# PCB-JACKGPO.net
KiCad netlist of a schematic drawn in EAGLE
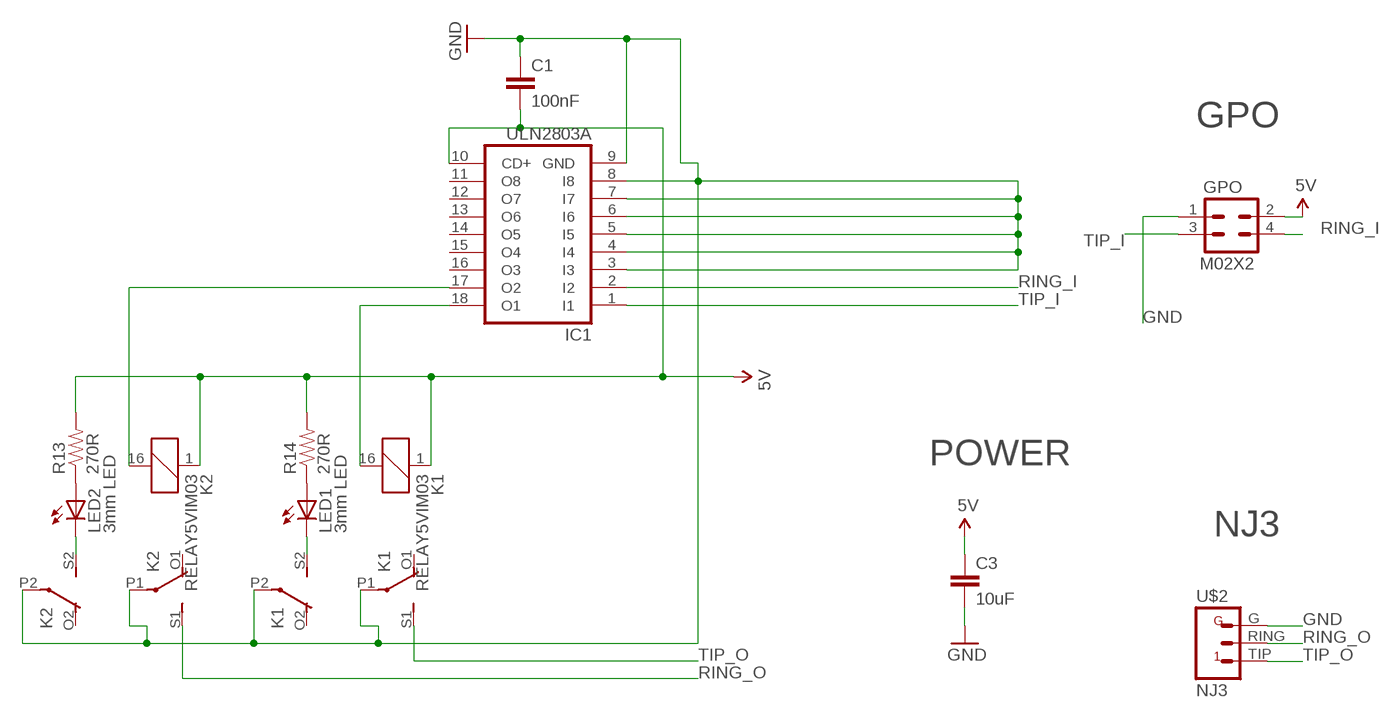
[diagram p0: schematic, sheet 1]

(export (version "E")
  (design (tool "Eeschema 10.0.6"))
  (components
    (comp (ref "C1")
      (value "100nF")
      (footprint "eagle-import:0805")
      (libsource (lib "eagle-import") (part "CAP0805"))
    )
    (comp (ref "C3")
      (value "10uF")
      (footprint "eagle-import:0805")
      (libsource (lib "eagle-import") (part "CAP0805"))
    )
    (comp (ref "GPO")
      (value "M02X2")
      (footprint "eagle-import:2X2")
      (libsource (lib "eagle-import") (part "M02X2"))
    )
    (comp (ref "IC1")
      (value "ULN2803A")
      (footprint "eagle-import:SO18W")
      (libsource (lib "eagle-import") (part "ULN2803ASO18W"))
    )
    (comp (ref "K1")
      (value "RELAY5VIM03")
      (footprint "eagle-import:DS2Y")
      (libsource (lib "eagle-import") (part "RELAY5VIM03"))
    )
    (comp (ref "K2")
      (value "RELAY5VIM03")
      (footprint "eagle-import:DS2Y")
      (libsource (lib "eagle-import") (part "RELAY5VIM03"))
    )
    (comp (ref "LED1")
      (value "3mm LED")
      (footprint "eagle-import:LED3MM")
      (libsource (lib "eagle-import") (part "LED3MM"))
    )
    (comp (ref "LED2")
      (value "3mm LED")
      (footprint "eagle-import:LED3MM")
      (libsource (lib "eagle-import") (part "LED3MM"))
    )
    (comp (ref "R13")
      (value "270R")
      (footprint "eagle-import:0603-RES")
      (libsource (lib "eagle-import") (part "RESISTOR0603-RES"))
    )
    (comp (ref "R14")
      (value "270R")
      (footprint "eagle-import:0603-RES")
      (libsource (lib "eagle-import") (part "RESISTOR0603-RES"))
    )
    (comp (ref "U$2")
      (value "NJ3")
      (footprint "eagle-import:NJ3FP6C")
      (libsource (lib "eagle-import") (part "NJ3"))
    )
  )
  (nets
    (net (code "1") (name "/RING_I") (class "Default")
      (node (ref "GPO") (pin "4") (pinfunction "4_4") (pintype "passive"))
      (node (ref "IC1") (pin "2") (pinfunction "I2_2") (pintype "input"))
    )
    (net (code "2") (name "/RING_O") (class "Default")
      (node (ref "K2") (pin "S1") (pinfunction "S_S1") (pintype "passive"))
      (node (ref "U$2") (pin "RING") (pinfunction "2_RING") (pintype "passive"))
    )
    (net (code "3") (name "/TIP_I") (class "Default")
      (node (ref "GPO") (pin "3") (pinfunction "3_3") (pintype "passive"))
      (node (ref "IC1") (pin "1") (pinfunction "I1_1") (pintype "input"))
    )
    (net (code "4") (name "/TIP_O") (class "Default")
      (node (ref "K1") (pin "S1") (pinfunction "S_S1") (pintype "passive"))
      (node (ref "U$2") (pin "TIP") (pinfunction "1_TIP") (pintype "passive"))
    )
    (net (code "5") (name "5V") (class "Default")
      (node (ref "C1") (pin "2") (pinfunction "2_2") (pintype "passive"))
      (node (ref "C3") (pin "1") (pinfunction "1_1") (pintype "passive"))
      (node (ref "GPO") (pin "2") (pinfunction "2_2") (pintype "passive"))
      (node (ref "IC1") (pin "10") (pinfunction "CD+_10") (pintype "passive"))
      (node (ref "K1") (pin "1") (pinfunction "1_1") (pintype "passive"))
      (node (ref "K2") (pin "1") (pinfunction "1_1") (pintype "passive"))
      (node (ref "R13") (pin "2") (pinfunction "2_2") (pintype "passive"))
      (node (ref "R14") (pin "2") (pinfunction "2_2") (pintype "passive"))
    )
    (net (code "6") (name "GND") (class "Default")
      (node (ref "C1") (pin "1") (pinfunction "1_1") (pintype "passive"))
      (node (ref "C3") (pin "2") (pinfunction "2_2") (pintype "passive"))
      (node (ref "GPO") (pin "1") (pinfunction "1_1") (pintype "passive"))
      (node (ref "IC1") (pin "3") (pinfunction "I3_3") (pintype "input"))
      (node (ref "IC1") (pin "4") (pinfunction "I4_4") (pintype "input"))
      (node (ref "IC1") (pin "5") (pinfunction "I5_5") (pintype "input"))
      (node (ref "IC1") (pin "6") (pinfunction "I6_6") (pintype "input"))
      (node (ref "IC1") (pin "7") (pinfunction "I7_7") (pintype "input"))
      (node (ref "IC1") (pin "8") (pinfunction "I8_8") (pintype "input"))
      (node (ref "IC1") (pin "9") (pinfunction "GND_9") (pintype "power_in"))
      (node (ref "K1") (pin "P1") (pinfunction "P_P1") (pintype "passive"))
      (node (ref "K1") (pin "P2") (pinfunction "P_P2") (pintype "passive"))
      (node (ref "K2") (pin "P1") (pinfunction "P_P1") (pintype "passive"))
      (node (ref "K2") (pin "P2") (pinfunction "P_P2") (pintype "passive"))
      (node (ref "U$2") (pin "G") (pinfunction "G_G") (pintype "power_in"))
    )
    (net (code "7") (name "Net-(IC1-O1)") (class "Default")
      (node (ref "IC1") (pin "18") (pinfunction "O1_18") (pintype "open_collector"))
      (node (ref "K1") (pin "16") (pinfunction "2_16") (pintype "passive"))
    )
    (net (code "8") (name "Net-(IC1-O2)") (class "Default")
      (node (ref "IC1") (pin "17") (pinfunction "O2_17") (pintype "open_collector"))
      (node (ref "K2") (pin "16") (pinfunction "2_16") (pintype "passive"))
    )
    (net (code "9") (name "Net-(K1C-S)") (class "Default")
      (node (ref "K1") (pin "S2") (pinfunction "S_S2") (pintype "passive"))
      (node (ref "LED1") (pin "K") (pinfunction "C_K") (pintype "passive"))
    )
    (net (code "10") (name "Net-(K2C-S)") (class "Default")
      (node (ref "K2") (pin "S2") (pinfunction "S_S2") (pintype "passive"))
      (node (ref "LED2") (pin "K") (pinfunction "C_K") (pintype "passive"))
    )
    (net (code "11") (name "Net-(LED1-PadA)") (class "Default")
      (node (ref "LED1") (pin "A") (pinfunction "A_A") (pintype "passive"))
      (node (ref "R14") (pin "1") (pinfunction "1_1") (pintype "passive"))
    )
    (net (code "12") (name "Net-(LED2-PadA)") (class "Default")
      (node (ref "LED2") (pin "A") (pinfunction "A_A") (pintype "passive"))
      (node (ref "R13") (pin "1") (pinfunction "1_1") (pintype "passive"))
    )
    (net (code "13") (name "unconnected-(IC1-O3-Pad16)") (class "Default")
      (node (ref "IC1") (pin "16") (pinfunction "O3_16") (pintype "open_collector"))
    )
    (net (code "14") (name "unconnected-(IC1-O4-Pad15)") (class "Default")
      (node (ref "IC1") (pin "15") (pinfunction "O4_15") (pintype "open_collector"))
    )
    (net (code "15") (name "unconnected-(IC1-O5-Pad14)") (class "Default")
      (node (ref "IC1") (pin "14") (pinfunction "O5_14") (pintype "open_collector"))
    )
    (net (code "16") (name "unconnected-(IC1-O6-Pad13)") (class "Default")
      (node (ref "IC1") (pin "13") (pinfunction "O6_13") (pintype "open_collector"))
    )
    (net (code "17") (name "unconnected-(IC1-O7-Pad12)") (class "Default")
      (node (ref "IC1") (pin "12") (pinfunction "O7_12") (pintype "open_collector"))
    )
    (net (code "18") (name "unconnected-(IC1-O8-Pad11)") (class "Default")
      (node (ref "IC1") (pin "11") (pinfunction "O8_11") (pintype "open_collector"))
    )
    (net (code "19") (name "unconnected-(K1B-O-PadO1)") (class "Default")
      (node (ref "K1") (pin "O1") (pinfunction "O_O1") (pintype "passive"))
    )
    (net (code "20") (name "unconnected-(K1C-O-PadO2)") (class "Default")
      (node (ref "K1") (pin "O2") (pinfunction "O_O2") (pintype "passive"))
    )
    (net (code "21") (name "unconnected-(K2B-O-PadO1)") (class "Default")
      (node (ref "K2") (pin "O1") (pinfunction "O_O1") (pintype "passive"))
    )
    (net (code "22") (name "unconnected-(K2C-O-PadO2)") (class "Default")
      (node (ref "K2") (pin "O2") (pinfunction "O_O2") (pintype "passive"))
    )
  )
)
